# UV_Sensor.net
KiCad netlist of a schematic drawn in Altium Designer
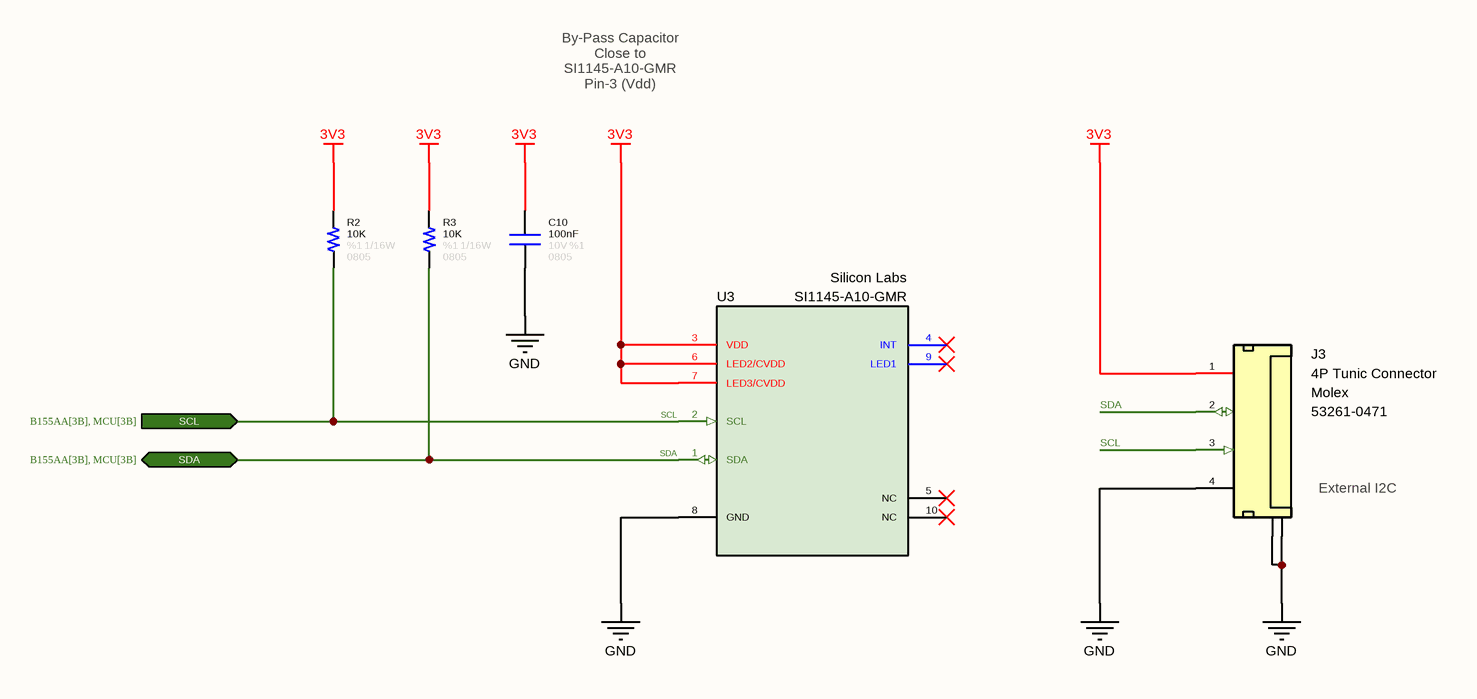
[diagram p0: UV Sensor.SchDoc]

(export (version "E")
  (design (tool "Eeschema 10.0.6"))
  (components
    (comp (ref "C10")
      (value "100nF")
      (footprint "CAPACITOR_0805")
      (description "Capacitor (MLCC) - 100nF / 10V / 0805")
      (fields
        (field (name "MANUFACTURER PART NUMBER") "C0805C104K8JACAUTO")
        (field (name "TOLERANCE") "%1")
        (field (name "VOLTAGE") "10V")
        (field (name "CASE") "0805")
        (field (name "Comment") "Capacitor - 100nF [0805] (MLCC)")
      )
      (libsource (lib "Akkoyun") (part "Capacitor - 100nF [0805-10V]"))
    )
    (comp (ref "J3")
      (value "4P SMD Tunic Connector")
      (footprint "Connector_Tunic 4P")
      (description "Mini Tunic Connector with 4P")
      (fields
        (field (name "MANUFACTURER NAME") "Molex")
        (field (name "MANUFACTURER PART NUMBER") "53261-0471")
      )
      (libsource (lib "Akkoyun") (part "Connector - Mini Tunic 4P (1.25)"))
    )
    (comp (ref "R2")
      (value "10K")
      (footprint "RESISTOR_0805")
      (description "Thick Film Resistors - SMD 1/16 W 10 KOhm 1%")
      (fields
        (field (name "MANUFACTURER PART NUMBER") "CRCW040210K0FKED")
        (field (name "TOLERANCE") "%1")
        (field (name "CASE") "0805")
        (field (name "POWER") "1/16W")
        (field (name "Comment") "10K - 0805 - %1 - 1/16W")
      )
      (libsource (lib "Akkoyun") (part "Resistor - 10K [0805]"))
    )
    (comp (ref "R3")
      (value "10K")
      (footprint "RESISTOR_0805")
      (description "Thick Film Resistors - SMD 1/16 W 10 KOhm 1%")
      (fields
        (field (name "MANUFACTURER PART NUMBER") "CRCW040210K0FKED")
        (field (name "TOLERANCE") "%1")
        (field (name "CASE") "0805")
        (field (name "POWER") "1/16W")
        (field (name "Comment") "10K - 0805 - %1 - 1/16W")
      )
      (libsource (lib "Akkoyun") (part "Resistor - 10K [0805]"))
    )
    (comp (ref "U3")
      (value "Si1145-A10-GMR")
      (footprint "SI1145")
      (description "Proximity Sensors I2C UV Index and Proximity/Ambient Light Sensor with 1 LED Driver")
      (fields
        (field (name "MANUFACTURER PART NUMBER") "SI1145-A10-GMR")
        (field (name "MANUFACTURER NAME") "Silicon Labs")
      )
      (libsource (lib "Akkoyun") (part "IC - Si1145-A10-GMR"))
    )
  )
  (nets
    (net (code "1") (name "/SCL") (class "Default")
      (node (ref "J3") (pin "3") (pinfunction "SCL_3") (pintype "input"))
      (node (ref "R2") (pin "1") (pinfunction "1_1") (pintype "passive"))
      (node (ref "U3") (pin "2") (pinfunction "SCL_2") (pintype "input"))
    )
    (net (code "2") (name "/SDA") (class "Default")
      (node (ref "J3") (pin "2") (pinfunction "SDA_2") (pintype "bidirectional"))
      (node (ref "R3") (pin "1") (pinfunction "1_1") (pintype "passive"))
      (node (ref "U3") (pin "1") (pinfunction "SDA_1") (pintype "bidirectional"))
    )
    (net (code "3") (name "3V3") (class "Default")
      (node (ref "C10") (pin "2") (pinfunction "2_2") (pintype "passive"))
      (node (ref "J3") (pin "1") (pinfunction "3V3_1") (pintype "passive"))
      (node (ref "R2") (pin "2") (pinfunction "2_2") (pintype "passive"))
      (node (ref "R3") (pin "2") (pinfunction "2_2") (pintype "passive"))
      (node (ref "U3") (pin "3") (pinfunction "VDD_3") (pintype "power_in"))
      (node (ref "U3") (pin "6") (pinfunction "LED2/CVDD_6") (pintype "power_in"))
      (node (ref "U3") (pin "7") (pinfunction "LED3/CVDD_7") (pintype "power_in"))
    )
    (net (code "4") (name "GND") (class "Default")
      (node (ref "C10") (pin "1") (pinfunction "1_1") (pintype "passive"))
      (node (ref "J3") (pin "4") (pinfunction "GND_4") (pintype "passive"))
      (node (ref "J3") (pin "5") (pinfunction "GND_5") (pintype "passive"))
      (node (ref "J3") (pin "6") (pinfunction "GND_6") (pintype "passive"))
      (node (ref "U3") (pin "8") (pinfunction "GND_8") (pintype "power_in"))
    )
    (net (code "5") (name "unconnected-(U3-INT-Pad4)") (class "Default")
      (node (ref "U3") (pin "4") (pinfunction "INT_4") (pintype "passive+no_connect"))
    )
    (net (code "6") (name "unconnected-(U3-LED1-Pad9)") (class "Default")
      (node (ref "U3") (pin "9") (pinfunction "LED1_9") (pintype "passive+no_connect"))
    )
    (net (code "7") (name "unconnected-(U3-NC-Pad5)") (class "Default")
      (node (ref "U3") (pin "5") (pinfunction "NC_5") (pintype "passive+no_connect"))
    )
    (net (code "8") (name "unconnected-(U3-NC-Pad10)") (class "Default")
      (node (ref "U3") (pin "10") (pinfunction "NC_10") (pintype "passive+no_connect"))
    )
  )
)
